# Power_Distribution.net
KiCad netlist of a schematic drawn in EAGLE
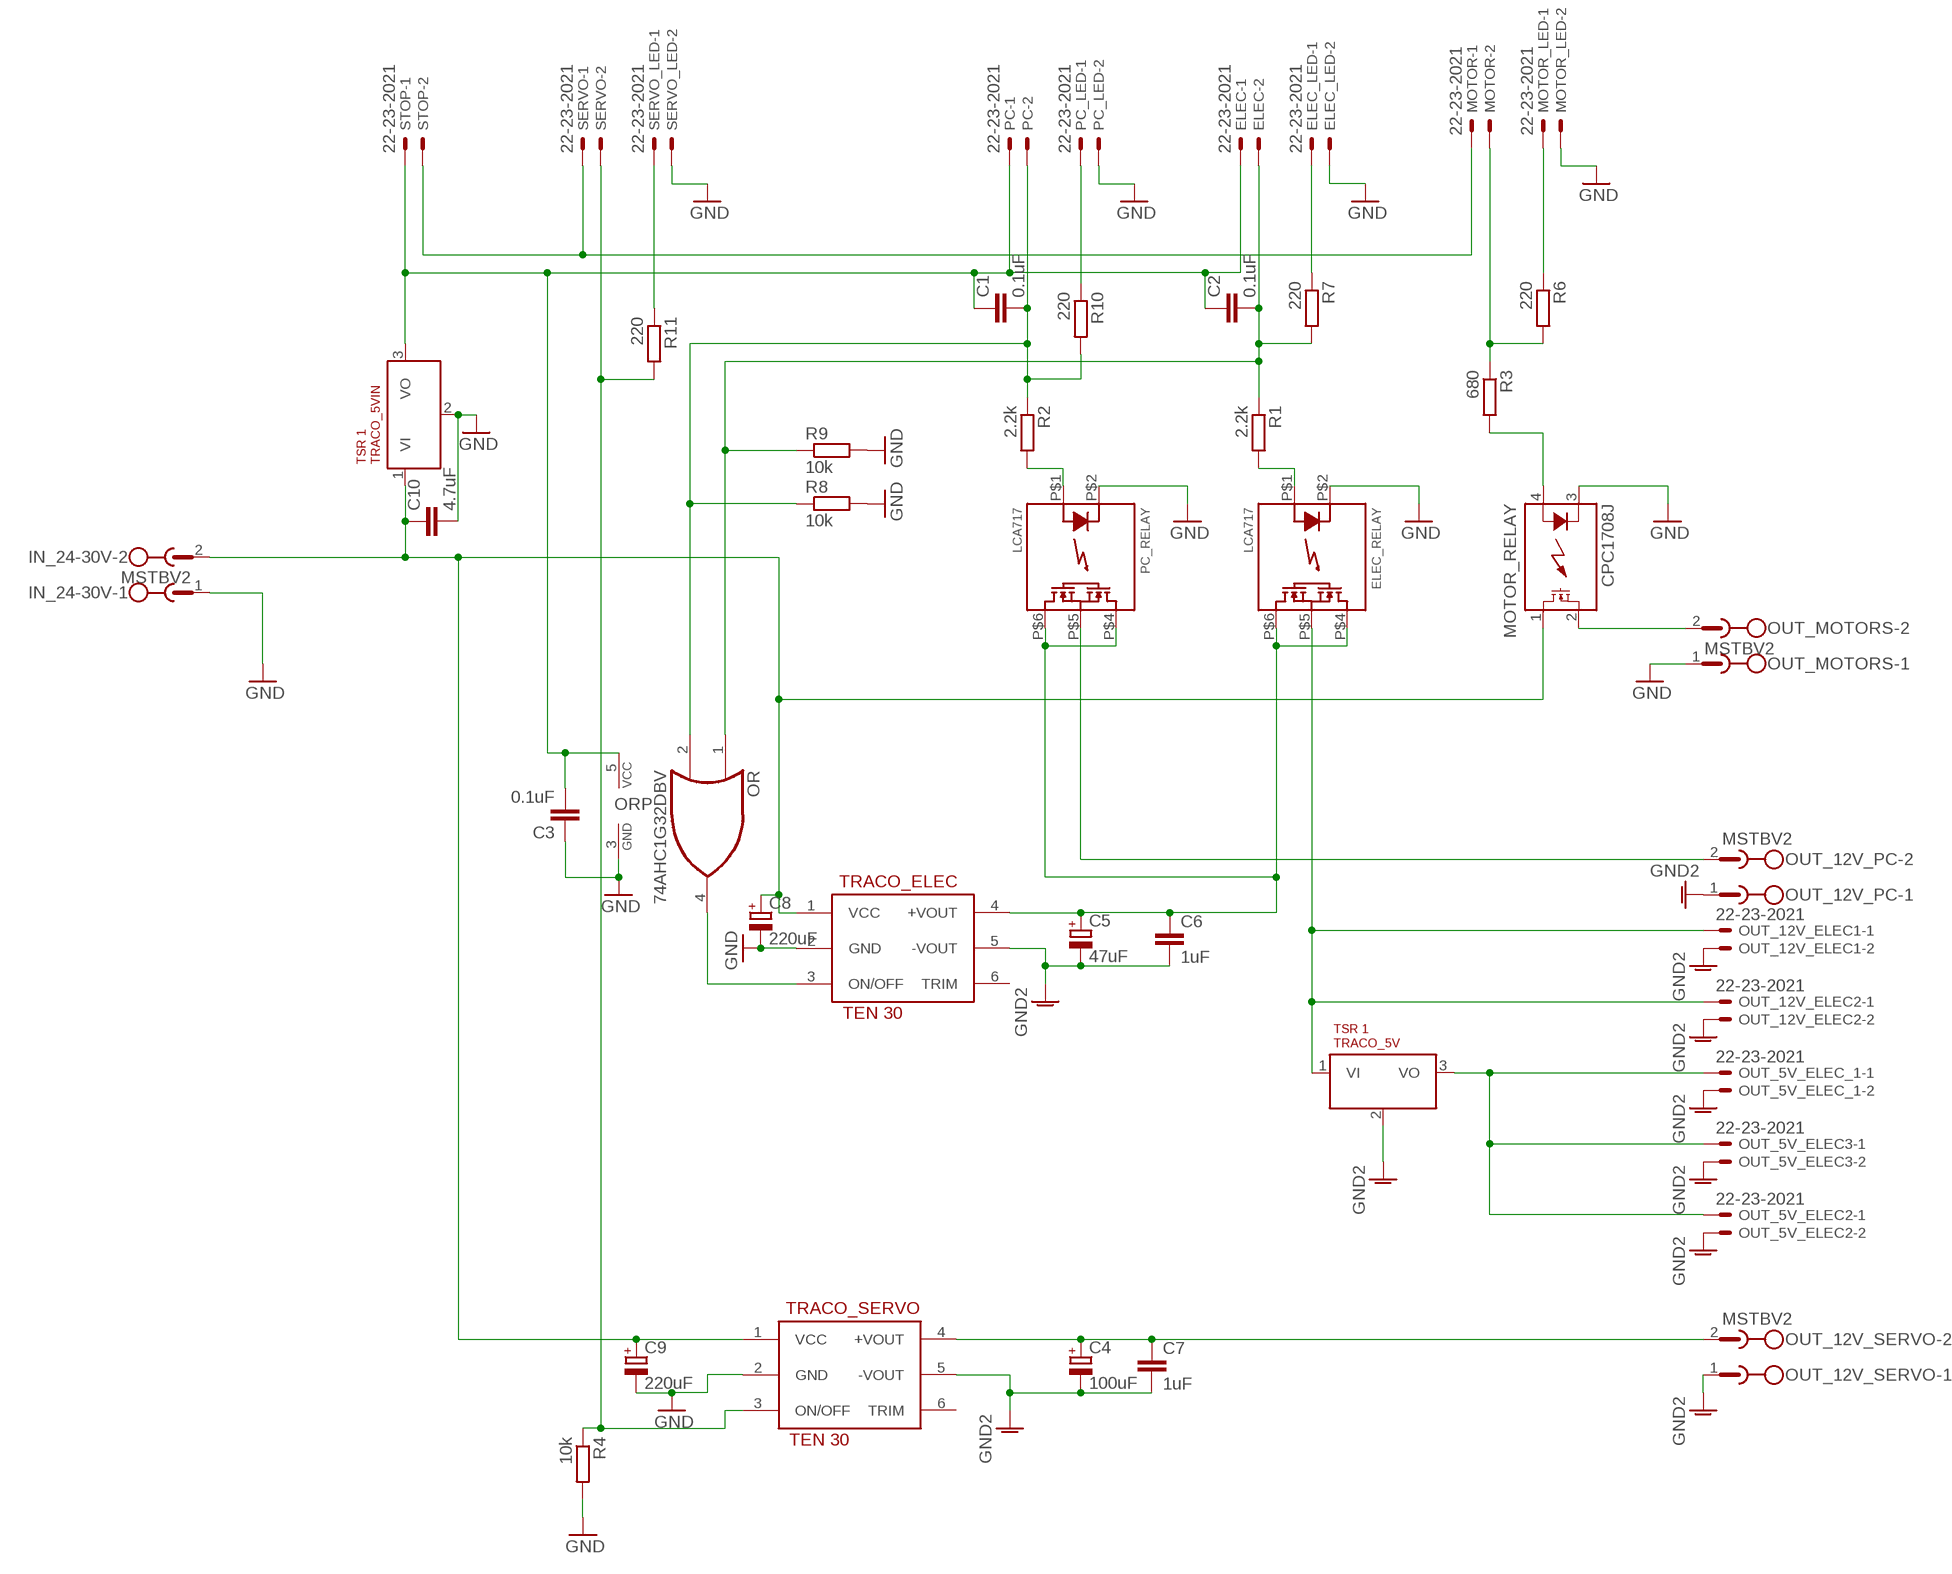
[diagram p0: schematic, sheet 1]

(export (version "E")
  (design (tool "Eeschema 10.0.6"))
  (components
    (comp (ref "C1")
      (value "0.1uF")
      (footprint "eagle-import:C0805")
      (libsource (lib "eagle-import") (part "C-EUC0805"))
    )
    (comp (ref "C2")
      (value "0.1uF")
      (footprint "eagle-import:C0805")
      (libsource (lib "eagle-import") (part "C-EUC0805"))
    )
    (comp (ref "C3")
      (value "0.1uF")
      (footprint "eagle-import:C0805")
      (libsource (lib "eagle-import") (part "C-EUC0805"))
    )
    (comp (ref "C4")
      (value "100uF")
      (footprint "eagle-import:E2-5")
      (libsource (lib "eagle-import") (part "CPOL-EUE2-5"))
    )
    (comp (ref "C5")
      (value "47uF")
      (footprint "eagle-import:E2-5")
      (libsource (lib "eagle-import") (part "CPOL-EUE2-5"))
    )
    (comp (ref "C6")
      (value "1uF")
      (footprint "eagle-import:C1206")
      (libsource (lib "eagle-import") (part "C-EUC1206"))
    )
    (comp (ref "C7")
      (value "1uF")
      (footprint "eagle-import:C1206")
      (libsource (lib "eagle-import") (part "C-EUC1206"))
    )
    (comp (ref "C8")
      (value "220uF")
      (footprint "eagle-import:E3,5-8")
      (libsource (lib "eagle-import") (part "CPOL-EUE3.5-8"))
    )
    (comp (ref "C9")
      (value "220uF")
      (footprint "eagle-import:E3,5-8")
      (libsource (lib "eagle-import") (part "CPOL-EUE3.5-8"))
    )
    (comp (ref "C10")
      (value "4.7uF")
      (footprint "eagle-import:C1210")
      (libsource (lib "eagle-import") (part "C-EUC1210"))
    )
    (comp (ref "ELEC")
      (value "22-23-2021")
      (footprint "eagle-import:22-23-2021")
      (fields (field (name "MF") "MOLEX"))
      (libsource (lib "eagle-import") (part "22-23-2021"))
    )
    (comp (ref "ELEC_LED")
      (value "22-23-2021")
      (footprint "eagle-import:22-23-2021")
      (fields (field (name "MF") "MOLEX"))
      (libsource (lib "eagle-import") (part "22-23-2021"))
    )
    (comp (ref "ELEC_RELAY")
      (value "LCA717")
      (footprint "eagle-import:DIP-6")
      (libsource (lib "eagle-import") (part "LCA717"))
    )
    (comp (ref "IN_24-30V")
      (value "MSTBV2")
      (footprint "eagle-import:MSTBV2")
      (fields (field (name "MPN") "MSTBV 2,5/2-GF-5.08"))
      (libsource (lib "eagle-import") (part "MSTBV2"))
    )
    (comp (ref "MOTOR")
      (value "22-23-2021")
      (footprint "eagle-import:22-23-2021")
      (fields (field (name "MF") "MOLEX"))
      (libsource (lib "eagle-import") (part "22-23-2021"))
    )
    (comp (ref "MOTOR_LED")
      (value "22-23-2021")
      (footprint "eagle-import:22-23-2021")
      (fields (field (name "MF") "MOLEX"))
      (libsource (lib "eagle-import") (part "22-23-2021"))
    )
    (comp (ref "MOTOR_RELAY")
      (value "CPC1708J")
      (footprint "eagle-import:I4-PAC")
      (libsource (lib "eagle-import") (part "CPC1708J"))
    )
    (comp (ref "OR")
      (value "74AHC1G32DBV")
      (footprint "eagle-import:SOT23-5")
      (libsource (lib "eagle-import") (part "741G32DBVAHC"))
    )
    (comp (ref "OUT_5V_ELEC2")
      (value "22-23-2021")
      (footprint "eagle-import:22-23-2021")
      (fields (field (name "MF") "MOLEX"))
      (libsource (lib "eagle-import") (part "22-23-2021"))
    )
    (comp (ref "OUT_5V_ELEC3")
      (value "22-23-2021")
      (footprint "eagle-import:22-23-2021")
      (fields (field (name "MF") "MOLEX"))
      (libsource (lib "eagle-import") (part "22-23-2021"))
    )
    (comp (ref "OUT_5V_ELEC_1")
      (value "22-23-2021")
      (footprint "eagle-import:22-23-2021")
      (fields (field (name "MF") "MOLEX"))
      (libsource (lib "eagle-import") (part "22-23-2021"))
    )
    (comp (ref "OUT_12V_ELEC1")
      (value "22-23-2021")
      (footprint "eagle-import:22-23-2021")
      (fields (field (name "MF") "MOLEX"))
      (libsource (lib "eagle-import") (part "22-23-2021"))
    )
    (comp (ref "OUT_12V_ELEC2")
      (value "22-23-2021")
      (footprint "eagle-import:22-23-2021")
      (fields (field (name "MF") "MOLEX"))
      (libsource (lib "eagle-import") (part "22-23-2021"))
    )
    (comp (ref "OUT_12V_PC")
      (value "MSTBV2")
      (footprint "eagle-import:MSTBV2")
      (fields (field (name "MPN") "MSTBV 2,5/2-GF-5.08"))
      (libsource (lib "eagle-import") (part "MSTBV2"))
    )
    (comp (ref "OUT_12V_SERVO")
      (value "MSTBV2")
      (footprint "eagle-import:MSTBV2")
      (fields (field (name "MPN") "MSTBV 2,5/2-GF-5.08"))
      (libsource (lib "eagle-import") (part "MSTBV2"))
    )
    (comp (ref "OUT_MOTORS")
      (value "MSTBV2")
      (footprint "eagle-import:MSTBV2")
      (fields (field (name "MPN") "MSTBV 2,5/2-GF-5.08"))
      (libsource (lib "eagle-import") (part "MSTBV2"))
    )
    (comp (ref "PC")
      (value "22-23-2021")
      (footprint "eagle-import:22-23-2021")
      (fields (field (name "MF") "MOLEX"))
      (libsource (lib "eagle-import") (part "22-23-2021"))
    )
    (comp (ref "PC_LED")
      (value "22-23-2021")
      (footprint "eagle-import:22-23-2021")
      (fields (field (name "MF") "MOLEX"))
      (libsource (lib "eagle-import") (part "22-23-2021"))
    )
    (comp (ref "PC_RELAY")
      (value "LCA717")
      (footprint "eagle-import:DIP-6")
      (libsource (lib "eagle-import") (part "LCA717"))
    )
    (comp (ref "R1")
      (value "2.2k")
      (footprint "eagle-import:R0805")
      (libsource (lib "eagle-import") (part "R-EU_R0805"))
    )
    (comp (ref "R2")
      (value "2.2k")
      (footprint "eagle-import:R0805")
      (libsource (lib "eagle-import") (part "R-EU_R0805"))
    )
    (comp (ref "R3")
      (value "680")
      (footprint "eagle-import:R0805")
      (libsource (lib "eagle-import") (part "R-EU_R0805"))
    )
    (comp (ref "R4")
      (value "10k")
      (footprint "eagle-import:R0805")
      (libsource (lib "eagle-import") (part "R-EU_R0805"))
    )
    (comp (ref "R6")
      (value "220")
      (footprint "eagle-import:R0805")
      (libsource (lib "eagle-import") (part "R-EU_R0805"))
    )
    (comp (ref "R7")
      (value "220")
      (footprint "eagle-import:R0805")
      (libsource (lib "eagle-import") (part "R-EU_R0805"))
    )
    (comp (ref "R8")
      (value "10k")
      (footprint "eagle-import:R0805")
      (libsource (lib "eagle-import") (part "R-EU_R0805"))
    )
    (comp (ref "R9")
      (value "10k")
      (footprint "eagle-import:R0805")
      (libsource (lib "eagle-import") (part "R-EU_R0805"))
    )
    (comp (ref "R10")
      (value "220")
      (footprint "eagle-import:R0805")
      (libsource (lib "eagle-import") (part "R-EU_R0805"))
    )
    (comp (ref "R11")
      (value "220")
      (footprint "eagle-import:R0805")
      (libsource (lib "eagle-import") (part "R-EU_R0805"))
    )
    (comp (ref "SERVO")
      (value "22-23-2021")
      (footprint "eagle-import:22-23-2021")
      (fields (field (name "MF") "MOLEX"))
      (libsource (lib "eagle-import") (part "22-23-2021"))
    )
    (comp (ref "SERVO_LED")
      (value "22-23-2021")
      (footprint "eagle-import:22-23-2021")
      (fields (field (name "MF") "MOLEX"))
      (libsource (lib "eagle-import") (part "22-23-2021"))
    )
    (comp (ref "STOP")
      (value "22-23-2021")
      (footprint "eagle-import:22-23-2021")
      (fields (field (name "MF") "MOLEX"))
      (libsource (lib "eagle-import") (part "22-23-2021"))
    )
    (comp (ref "TRACO_5V")
      (value "TSR-1")
      (footprint "eagle-import:TRACO-TO220")
      (libsource (lib "eagle-import") (part "TSR-1"))
    )
    (comp (ref "TRACO_5VIN")
      (value "TSR-1")
      (footprint "eagle-import:TRACO-TO220")
      (libsource (lib "eagle-import") (part "TSR-1"))
    )
    (comp (ref "TRACO_ELEC")
      (value "TEN-30")
      (footprint "eagle-import:TRACO2X1")
      (libsource (lib "eagle-import") (part "TEN-30"))
    )
    (comp (ref "TRACO_SERVO")
      (value "TEN-50")
      (footprint "eagle-import:TRACO2X1")
      (libsource (lib "eagle-import") (part "TEN-30"))
    )
  )
  (nets
    (net (code "1") (name "GND") (class "Default")
      (node (ref "C10") (pin "2") (pinfunction "2_2") (pintype "passive"))
      (node (ref "C3") (pin "1") (pinfunction "1_1") (pintype "passive"))
      (node (ref "C8") (pin "-") (pinfunction "-_-") (pintype "passive"))
      (node (ref "C9") (pin "-") (pinfunction "-_-") (pintype "passive"))
      (node (ref "ELEC_LED") (pin "2") (pinfunction "S_2") (pintype "passive"))
      (node (ref "ELEC_RELAY") (pin "P$2") (pinfunction "2_P$2") (pintype "bidirectional"))
      (node (ref "IN_24-30V") (pin "1") (pinfunction "1_1") (pintype "passive"))
      (node (ref "MOTOR_LED") (pin "2") (pinfunction "S_2") (pintype "passive"))
      (node (ref "MOTOR_RELAY") (pin "3") (pinfunction "K_3") (pintype "passive"))
      (node (ref "OR") (pin "3") (pinfunction "GND_3") (pintype "power_in"))
      (node (ref "OUT_MOTORS") (pin "1") (pinfunction "1_1") (pintype "passive"))
      (node (ref "PC_LED") (pin "2") (pinfunction "S_2") (pintype "passive"))
      (node (ref "PC_RELAY") (pin "P$2") (pinfunction "2_P$2") (pintype "bidirectional"))
      (node (ref "R4") (pin "2") (pinfunction "2_2") (pintype "passive"))
      (node (ref "R8") (pin "2") (pinfunction "2_2") (pintype "passive"))
      (node (ref "R9") (pin "2") (pinfunction "2_2") (pintype "passive"))
      (node (ref "SERVO_LED") (pin "2") (pinfunction "S_2") (pintype "passive"))
      (node (ref "TRACO_5VIN") (pin "2") (pinfunction "GND_2") (pintype "bidirectional"))
      (node (ref "TRACO_ELEC") (pin "2") (pinfunction "GND_2") (pintype "bidirectional"))
      (node (ref "TRACO_SERVO") (pin "2") (pinfunction "GND_2") (pintype "bidirectional"))
    )
    (net (code "2") (name "GND2") (class "Default")
      (node (ref "C4") (pin "-") (pinfunction "-_-") (pintype "passive"))
      (node (ref "C5") (pin "-") (pinfunction "-_-") (pintype "passive"))
      (node (ref "C6") (pin "2") (pinfunction "2_2") (pintype "passive"))
      (node (ref "C7") (pin "2") (pinfunction "2_2") (pintype "passive"))
      (node (ref "OUT_12V_ELEC1") (pin "2") (pinfunction "S_2") (pintype "passive"))
      (node (ref "OUT_12V_ELEC2") (pin "2") (pinfunction "S_2") (pintype "passive"))
      (node (ref "OUT_12V_PC") (pin "1") (pinfunction "1_1") (pintype "passive"))
      (node (ref "OUT_12V_SERVO") (pin "1") (pinfunction "1_1") (pintype "passive"))
      (node (ref "OUT_5V_ELEC2") (pin "2") (pinfunction "S_2") (pintype "passive"))
      (node (ref "OUT_5V_ELEC3") (pin "2") (pinfunction "S_2") (pintype "passive"))
      (node (ref "OUT_5V_ELEC_1") (pin "2") (pinfunction "S_2") (pintype "passive"))
      (node (ref "TRACO_5V") (pin "2") (pinfunction "GND_2") (pintype "bidirectional"))
      (node (ref "TRACO_ELEC") (pin "5") (pinfunction "-VOUT_5") (pintype "bidirectional"))
      (node (ref "TRACO_SERVO") (pin "5") (pinfunction "-VOUT_5") (pintype "bidirectional"))
    )
    (net (code "3") (name "Net-(ELECA-S)") (class "Default")
      (node (ref "C1") (pin "1") (pinfunction "1_1") (pintype "passive"))
      (node (ref "C2") (pin "1") (pinfunction "1_1") (pintype "passive"))
      (node (ref "C3") (pin "2") (pinfunction "2_2") (pintype "passive"))
      (node (ref "ELEC") (pin "1") (pinfunction "S_1") (pintype "passive"))
      (node (ref "OR") (pin "5") (pinfunction "VCC_5") (pintype "power_in"))
      (node (ref "PC") (pin "1") (pinfunction "S_1") (pintype "passive"))
      (node (ref "STOP") (pin "1") (pinfunction "S_1") (pintype "passive"))
      (node (ref "TRACO_5VIN") (pin "3") (pinfunction "VO_3") (pintype "bidirectional"))
    )
    (net (code "4") (name "Net-(ELECB-S)") (class "Default")
      (node (ref "C2") (pin "2") (pinfunction "2_2") (pintype "passive"))
      (node (ref "ELEC") (pin "2") (pinfunction "S_2") (pintype "passive"))
      (node (ref "OR") (pin "1") (pinfunction "I0_1") (pintype "input"))
      (node (ref "R1") (pin "1") (pinfunction "1_1") (pintype "passive"))
      (node (ref "R7") (pin "2") (pinfunction "2_2") (pintype "passive"))
      (node (ref "R9") (pin "1") (pinfunction "1_1") (pintype "passive"))
    )
    (net (code "5") (name "Net-(ELEC_LEDA-S)") (class "Default")
      (node (ref "ELEC_LED") (pin "1") (pinfunction "S_1") (pintype "passive"))
      (node (ref "R7") (pin "1") (pinfunction "1_1") (pintype "passive"))
    )
    (net (code "6") (name "Net-(ELEC_RELAY-1)") (class "Default")
      (node (ref "ELEC_RELAY") (pin "P$1") (pinfunction "1_P$1") (pintype "bidirectional"))
      (node (ref "R1") (pin "2") (pinfunction "2_2") (pintype "passive"))
    )
    (net (code "7") (name "Net-(ELEC_RELAY-4)") (class "Default")
      (node (ref "C5") (pin "+") (pinfunction "+_+") (pintype "passive"))
      (node (ref "C6") (pin "1") (pinfunction "1_1") (pintype "passive"))
      (node (ref "ELEC_RELAY") (pin "P$4") (pinfunction "4_P$4") (pintype "bidirectional"))
      (node (ref "ELEC_RELAY") (pin "P$6") (pinfunction "6_P$6") (pintype "bidirectional"))
      (node (ref "PC_RELAY") (pin "P$4") (pinfunction "4_P$4") (pintype "bidirectional"))
      (node (ref "PC_RELAY") (pin "P$6") (pinfunction "6_P$6") (pintype "bidirectional"))
      (node (ref "TRACO_ELEC") (pin "4") (pinfunction "+VOUT_4") (pintype "bidirectional"))
    )
    (net (code "8") (name "Net-(ELEC_RELAY-5)") (class "Default")
      (node (ref "ELEC_RELAY") (pin "P$5") (pinfunction "5_P$5") (pintype "bidirectional"))
      (node (ref "OUT_12V_ELEC1") (pin "1") (pinfunction "S_1") (pintype "passive"))
      (node (ref "OUT_12V_ELEC2") (pin "1") (pinfunction "S_1") (pintype "passive"))
      (node (ref "TRACO_5V") (pin "1") (pinfunction "VI_1") (pintype "bidirectional"))
    )
    (net (code "9") (name "Net-(IN_24-30VB-1)") (class "Default")
      (node (ref "C10") (pin "1") (pinfunction "1_1") (pintype "passive"))
      (node (ref "C8") (pin "+") (pinfunction "+_+") (pintype "passive"))
      (node (ref "C9") (pin "+") (pinfunction "+_+") (pintype "passive"))
      (node (ref "IN_24-30V") (pin "2") (pinfunction "1_2") (pintype "passive"))
      (node (ref "MOTOR_RELAY") (pin "1") (pinfunction "DS1_1") (pintype "passive"))
      (node (ref "TRACO_5VIN") (pin "1") (pinfunction "VI_1") (pintype "bidirectional"))
      (node (ref "TRACO_ELEC") (pin "1") (pinfunction "VCC_1") (pintype "bidirectional"))
      (node (ref "TRACO_SERVO") (pin "1") (pinfunction "VCC_1") (pintype "bidirectional"))
    )
    (net (code "10") (name "Net-(MOTORA-S)") (class "Default")
      (node (ref "MOTOR") (pin "1") (pinfunction "S_1") (pintype "passive"))
      (node (ref "SERVO") (pin "1") (pinfunction "S_1") (pintype "passive"))
      (node (ref "STOP") (pin "2") (pinfunction "S_2") (pintype "passive"))
    )
    (net (code "11") (name "Net-(MOTORB-S)") (class "Default")
      (node (ref "MOTOR") (pin "2") (pinfunction "S_2") (pintype "passive"))
      (node (ref "R3") (pin "1") (pinfunction "1_1") (pintype "passive"))
      (node (ref "R6") (pin "2") (pinfunction "2_2") (pintype "passive"))
    )
    (net (code "12") (name "Net-(MOTOR_LEDA-S)") (class "Default")
      (node (ref "MOTOR_LED") (pin "1") (pinfunction "S_1") (pintype "passive"))
      (node (ref "R6") (pin "1") (pinfunction "1_1") (pintype "passive"))
    )
    (net (code "13") (name "Net-(MOTOR_RELAY-A)") (class "Default")
      (node (ref "MOTOR_RELAY") (pin "4") (pinfunction "A_4") (pintype "passive"))
      (node (ref "R3") (pin "2") (pinfunction "2_2") (pintype "passive"))
    )
    (net (code "14") (name "Net-(MOTOR_RELAY-DS2)") (class "Default")
      (node (ref "MOTOR_RELAY") (pin "2") (pinfunction "DS2_2") (pintype "passive"))
      (node (ref "OUT_MOTORS") (pin "2") (pinfunction "1_2") (pintype "passive"))
    )
    (net (code "15") (name "Net-(ORA-I1)") (class "Default")
      (node (ref "C1") (pin "2") (pinfunction "2_2") (pintype "passive"))
      (node (ref "OR") (pin "2") (pinfunction "I1_2") (pintype "input"))
      (node (ref "PC") (pin "2") (pinfunction "S_2") (pintype "passive"))
      (node (ref "R10") (pin "2") (pinfunction "2_2") (pintype "passive"))
      (node (ref "R2") (pin "1") (pinfunction "1_1") (pintype "passive"))
      (node (ref "R8") (pin "1") (pinfunction "1_1") (pintype "passive"))
    )
    (net (code "16") (name "Net-(ORA-O)") (class "Default")
      (node (ref "OR") (pin "4") (pinfunction "O_4") (pintype "output"))
      (node (ref "TRACO_ELEC") (pin "3") (pinfunction "ON/OFF_3") (pintype "bidirectional"))
    )
    (net (code "17") (name "Net-(OUT_5V_ELEC2A-S)") (class "Default")
      (node (ref "OUT_5V_ELEC2") (pin "1") (pinfunction "S_1") (pintype "passive"))
      (node (ref "OUT_5V_ELEC3") (pin "1") (pinfunction "S_1") (pintype "passive"))
      (node (ref "OUT_5V_ELEC_1") (pin "1") (pinfunction "S_1") (pintype "passive"))
      (node (ref "TRACO_5V") (pin "3") (pinfunction "VO_3") (pintype "bidirectional"))
    )
    (net (code "18") (name "Net-(OUT_12V_PCB-1)") (class "Default")
      (node (ref "OUT_12V_PC") (pin "2") (pinfunction "1_2") (pintype "passive"))
      (node (ref "PC_RELAY") (pin "P$5") (pinfunction "5_P$5") (pintype "bidirectional"))
    )
    (net (code "19") (name "Net-(OUT_12V_SERVOB-1)") (class "Default")
      (node (ref "C4") (pin "+") (pinfunction "+_+") (pintype "passive"))
      (node (ref "C7") (pin "1") (pinfunction "1_1") (pintype "passive"))
      (node (ref "OUT_12V_SERVO") (pin "2") (pinfunction "1_2") (pintype "passive"))
      (node (ref "TRACO_SERVO") (pin "4") (pinfunction "+VOUT_4") (pintype "bidirectional"))
    )
    (net (code "20") (name "Net-(PC_LEDA-S)") (class "Default")
      (node (ref "PC_LED") (pin "1") (pinfunction "S_1") (pintype "passive"))
      (node (ref "R10") (pin "1") (pinfunction "1_1") (pintype "passive"))
    )
    (net (code "21") (name "Net-(PC_RELAY-1)") (class "Default")
      (node (ref "PC_RELAY") (pin "P$1") (pinfunction "1_P$1") (pintype "bidirectional"))
      (node (ref "R2") (pin "2") (pinfunction "2_2") (pintype "passive"))
    )
    (net (code "22") (name "Net-(SERVOB-S)") (class "Default")
      (node (ref "R11") (pin "2") (pinfunction "2_2") (pintype "passive"))
      (node (ref "R4") (pin "1") (pinfunction "1_1") (pintype "passive"))
      (node (ref "SERVO") (pin "2") (pinfunction "S_2") (pintype "passive"))
      (node (ref "TRACO_SERVO") (pin "3") (pinfunction "ON/OFF_3") (pintype "bidirectional"))
    )
    (net (code "23") (name "Net-(SERVO_LEDA-S)") (class "Default")
      (node (ref "R11") (pin "1") (pinfunction "1_1") (pintype "passive"))
      (node (ref "SERVO_LED") (pin "1") (pinfunction "S_1") (pintype "passive"))
    )
    (net (code "24") (name "unconnected-(TRACO_ELEC-TRIM-Pad6)") (class "Default")
      (node (ref "TRACO_ELEC") (pin "6") (pinfunction "TRIM_6") (pintype "bidirectional"))
    )
    (net (code "25") (name "unconnected-(TRACO_SERVO-TRIM-Pad6)") (class "Default")
      (node (ref "TRACO_SERVO") (pin "6") (pinfunction "TRIM_6") (pintype "bidirectional"))
    )
  )
)
